# SolarPanel7Cells.net
KiCad netlist of a schematic drawn in Altium Designer
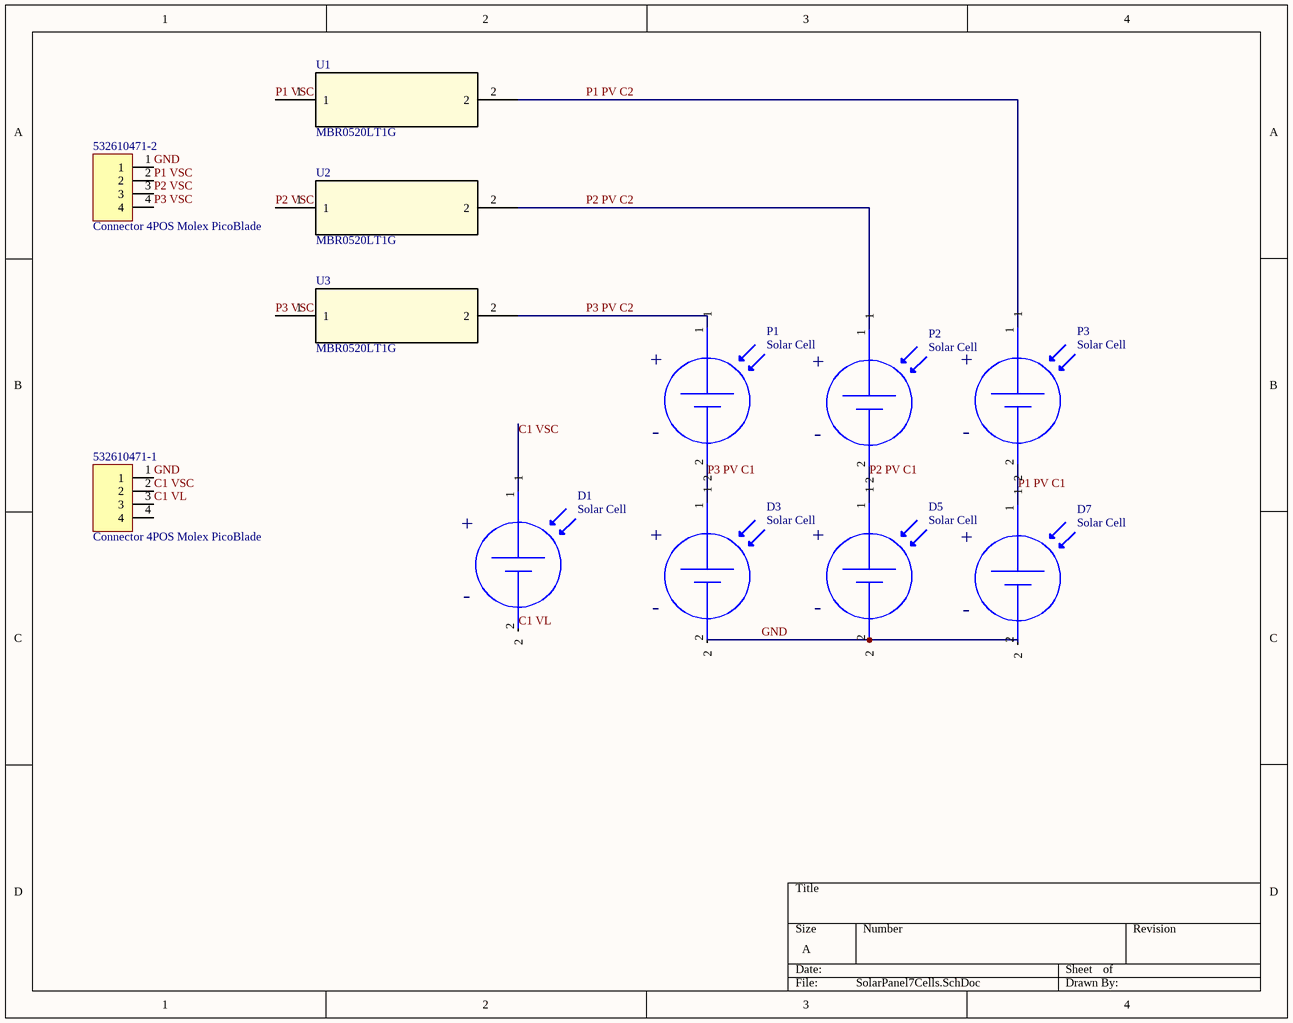
[diagram p0: SolarPanel7Cells.SchDoc]

(export (version "E")
  (design (tool "Eeschema 10.0.6"))
  (components
    (comp (ref "532610471-1")
      (value "Connector 4POS Molex PicoBlade")
      (footprint "532610471")
      (libsource (lib "SolarPanelZPlus") (part "532610471"))
    )
    (comp (ref "532610471-2")
      (value "Connector 4POS Molex PicoBlade")
      (footprint "532610471")
      (libsource (lib "SolarPanelZPlus") (part "532610471"))
    )
    (comp (ref "D1")
      (value "Solar Cell")
      (footprint "SolAeroBJT")
      (description "SolAero BJT Space Solar Cell")
      (libsource (lib "SolarPanelZPlus") (part "SolAeroBJT1"))
    )
    (comp (ref "D3")
      (value "Solar Cell")
      (footprint "SolAeroBJT")
      (description "SolAero BJT Space Solar Cell")
      (libsource (lib "SolarPanelZPlus") (part "SolAeroBJT1"))
    )
    (comp (ref "D5")
      (value "Solar Cell")
      (footprint "SolAeroBJT")
      (description "SolAero BJT Space Solar Cell")
      (libsource (lib "SolarPanelZPlus") (part "SolAeroBJT1"))
    )
    (comp (ref "D7")
      (value "Solar Cell")
      (footprint "SolAeroBJT")
      (description "SolAero BJT Space Solar Cell")
      (libsource (lib "SolarPanelZPlus") (part "SolAeroBJT1"))
    )
    (comp (ref "P1")
      (value "Solar Cell")
      (footprint "SolAeroBJT")
      (description "SolAero BJT Space Solar Cell")
      (libsource (lib "SolarPanelZPlus") (part "SolAeroBJT1"))
    )
    (comp (ref "P2")
      (value "Solar Cell")
      (footprint "SolAeroBJT")
      (description "SolAero BJT Space Solar Cell")
      (libsource (lib "SolarPanelZPlus") (part "SolAeroBJT1"))
    )
    (comp (ref "P3")
      (value "Solar Cell")
      (footprint "SolAeroBJT")
      (description "SolAero BJT Space Solar Cell")
      (libsource (lib "SolarPanelZPlus") (part "SolAeroBJT1"))
    )
    (comp (ref "U1")
      (value "MBR0520LT1G")
      (footprint "SOD-123")
      (description "Imported")
      (fields (field (name "COPYRIGHT") "Copyright (C) 2015 Accelerated Designs. All rights reserved"))
      (libsource (lib "SolarPanelZPlus") (part "MBR0520LT1G"))
    )
    (comp (ref "U2")
      (value "MBR0520LT1G")
      (footprint "SOD-123")
      (description "Imported")
      (fields (field (name "COPYRIGHT") "Copyright (C) 2015 Accelerated Designs. All rights reserved"))
      (libsource (lib "SolarPanelZPlus") (part "MBR0520LT1G"))
    )
    (comp (ref "U3")
      (value "MBR0520LT1G")
      (footprint "SOD-123")
      (description "Imported")
      (fields (field (name "COPYRIGHT") "Copyright (C) 2015 Accelerated Designs. All rights reserved"))
      (libsource (lib "SolarPanelZPlus") (part "MBR0520LT1G"))
    )
  )
  (nets
    (net (code "1") (name "/C1 VL") (class "Default")
      (node (ref "532610471-1") (pin "3") (pinfunction "3_3") (pintype "passive"))
      (node (ref "D1") (pin "2") (pinfunction "2_2") (pintype "passive"))
    )
    (net (code "2") (name "/C1 VSC") (class "Default")
      (node (ref "532610471-1") (pin "2") (pinfunction "2_2") (pintype "passive"))
      (node (ref "D1") (pin "1") (pinfunction "1_1") (pintype "power_in"))
    )
    (net (code "3") (name "/GND") (class "Default")
      (node (ref "532610471-1") (pin "1") (pinfunction "1_1") (pintype "passive"))
      (node (ref "532610471-2") (pin "1") (pinfunction "1_1") (pintype "passive"))
      (node (ref "D3") (pin "2") (pinfunction "2_2") (pintype "passive"))
      (node (ref "D5") (pin "2") (pinfunction "2_2") (pintype "passive"))
      (node (ref "D7") (pin "2") (pinfunction "2_2") (pintype "passive"))
    )
    (net (code "4") (name "/P1 PV C1") (class "Default")
      (node (ref "D7") (pin "1") (pinfunction "1_1") (pintype "power_in"))
      (node (ref "P3") (pin "2") (pinfunction "2_2") (pintype "passive"))
    )
    (net (code "5") (name "/P1 PV C2") (class "Default")
      (node (ref "P3") (pin "1") (pinfunction "1_1") (pintype "power_in"))
      (node (ref "U1") (pin "2") (pinfunction "2_2") (pintype "passive"))
    )
    (net (code "6") (name "/P1 VSC") (class "Default")
      (node (ref "532610471-2") (pin "2") (pinfunction "2_2") (pintype "passive"))
      (node (ref "U1") (pin "1") (pinfunction "1_1") (pintype "passive"))
    )
    (net (code "7") (name "/P2 PV C1") (class "Default")
      (node (ref "D5") (pin "1") (pinfunction "1_1") (pintype "power_in"))
      (node (ref "P2") (pin "2") (pinfunction "2_2") (pintype "passive"))
    )
    (net (code "8") (name "/P2 PV C2") (class "Default")
      (node (ref "P2") (pin "1") (pinfunction "1_1") (pintype "power_in"))
      (node (ref "U2") (pin "2") (pinfunction "2_2") (pintype "passive"))
    )
    (net (code "9") (name "/P2 VSC") (class "Default")
      (node (ref "532610471-2") (pin "3") (pinfunction "3_3") (pintype "passive"))
      (node (ref "U2") (pin "1") (pinfunction "1_1") (pintype "passive"))
    )
    (net (code "10") (name "/P3 PV C1") (class "Default")
      (node (ref "D3") (pin "1") (pinfunction "1_1") (pintype "power_in"))
      (node (ref "P1") (pin "2") (pinfunction "2_2") (pintype "passive"))
    )
    (net (code "11") (name "/P3 PV C2") (class "Default")
      (node (ref "P1") (pin "1") (pinfunction "1_1") (pintype "power_in"))
      (node (ref "U3") (pin "2") (pinfunction "2_2") (pintype "passive"))
    )
    (net (code "12") (name "/P3 VSC") (class "Default")
      (node (ref "532610471-2") (pin "4") (pinfunction "4_4") (pintype "passive"))
      (node (ref "U3") (pin "1") (pinfunction "1_1") (pintype "passive"))
    )
    (net (code "13") (name "unconnected-(532610471-1-Pad4)") (class "Default")
      (node (ref "532610471-1") (pin "4") (pinfunction "4_4") (pintype "passive"))
    )
  )
)
